# Decoder.net
KiCad netlist of a schematic drawn in EAGLE
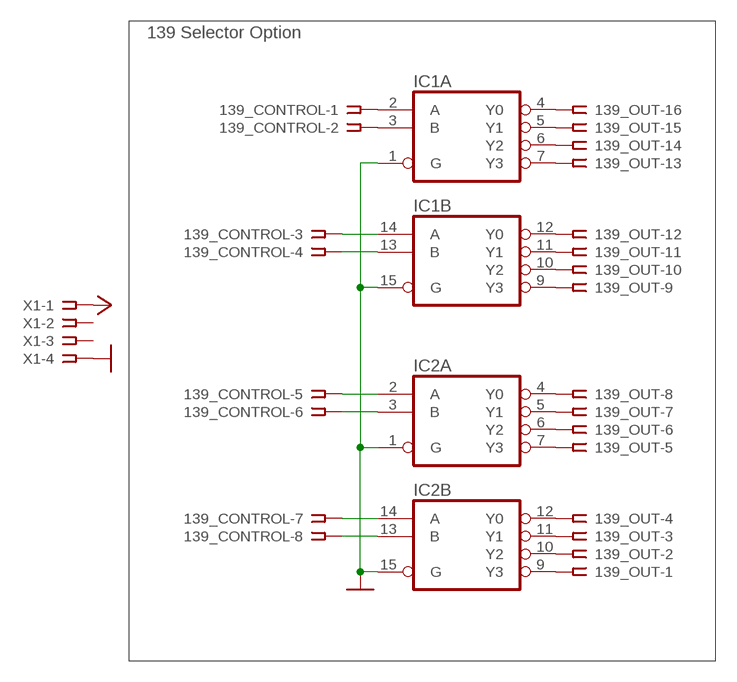
[diagram p0: schematic, sheet 1]

(export (version "E")
  (design (tool "Eeschema 10.0.6"))
  (components
    (comp (ref "139_CONTROL")
      (value "SSW-108-02-G-S")
      (footprint "eagle-import:SSW-108-02-G-S")
      (fields (field (name "MF") "Samtec Inc."))
      (libsource (lib "eagle-import") (part "SSW-108-02-G-S"))
    )
    (comp (ref "139_OUT")
      (value "SSW-116-02-G-S")
      (footprint "eagle-import:SSW-116-02-G-S")
      (fields (field (name "MF") "Samtec Inc."))
      (libsource (lib "eagle-import") (part "SSW-116-02-G-S"))
    )
    (comp (ref "IC1")
      (value "74AC139N")
      (footprint "eagle-import:DIL16")
      (libsource (lib "eagle-import") (part "74139NAC"))
    )
    (comp (ref "IC2")
      (value "74AC139N")
      (footprint "eagle-import:DIL16")
      (libsource (lib "eagle-import") (part "74139NAC"))
    )
    (comp (ref "X1")
      (value "SSW-104-02-G-S")
      (footprint "eagle-import:SSW-104-02-G-S")
      (fields (field (name "MF") "Samtec Inc."))
      (libsource (lib "eagle-import") (part "SSW-104-02-G-S"))
    )
  )
  (nets
    (net (code "1") (name "GND") (class "Default")
      (node (ref "IC1") (pin "1") (pinfunction "G_1") (pintype "input"))
      (node (ref "IC1") (pin "15") (pinfunction "G_15") (pintype "input"))
      (node (ref "IC2") (pin "1") (pinfunction "G_1") (pintype "input"))
      (node (ref "IC2") (pin "15") (pinfunction "G_15") (pintype "input"))
      (node (ref "X1") (pin "4") (pinfunction "1_4") (pintype "passive"))
    )
    (net (code "2") (name "Net-(139_CONTROLB-1)") (class "Default")
      (node (ref "139_CONTROL") (pin "2") (pinfunction "1_2") (pintype "passive"))
      (node (ref "IC1") (pin "3") (pinfunction "B_3") (pintype "input"))
    )
    (net (code "3") (name "Net-(139_CONTROLC-1)") (class "Default")
      (node (ref "139_CONTROL") (pin "3") (pinfunction "1_3") (pintype "passive"))
      (node (ref "IC1") (pin "14") (pinfunction "A_14") (pintype "input"))
    )
    (net (code "4") (name "Net-(139_CONTROLD-1)") (class "Default")
      (node (ref "139_CONTROL") (pin "4") (pinfunction "1_4") (pintype "passive"))
      (node (ref "IC1") (pin "13") (pinfunction "B_13") (pintype "input"))
    )
    (net (code "5") (name "Net-(139_CONTROLE-1)") (class "Default")
      (node (ref "139_CONTROL") (pin "5") (pinfunction "1_5") (pintype "passive"))
      (node (ref "IC2") (pin "2") (pinfunction "A_2") (pintype "input"))
    )
    (net (code "6") (name "Net-(139_CONTROLF-1)") (class "Default")
      (node (ref "139_CONTROL") (pin "6") (pinfunction "1_6") (pintype "passive"))
      (node (ref "IC2") (pin "3") (pinfunction "B_3") (pintype "input"))
    )
    (net (code "7") (name "Net-(139_CONTROLG-1)") (class "Default")
      (node (ref "139_CONTROL") (pin "7") (pinfunction "1_7") (pintype "passive"))
      (node (ref "IC2") (pin "14") (pinfunction "A_14") (pintype "input"))
    )
    (net (code "8") (name "Net-(139_CONTROLH-1)") (class "Default")
      (node (ref "139_CONTROL") (pin "8") (pinfunction "1_8") (pintype "passive"))
      (node (ref "IC2") (pin "13") (pinfunction "B_13") (pintype "input"))
    )
    (net (code "9") (name "Net-(139_OUTB-1)") (class "Default")
      (node (ref "139_OUT") (pin "10") (pinfunction "1_10") (pintype "passive"))
      (node (ref "IC1") (pin "10") (pinfunction "Y2_10") (pintype "output"))
    )
    (net (code "10") (name "Net-(139_OUTC-1)") (class "Default")
      (node (ref "139_OUT") (pin "11") (pinfunction "1_11") (pintype "passive"))
      (node (ref "IC1") (pin "11") (pinfunction "Y1_11") (pintype "output"))
    )
    (net (code "11") (name "Net-(139_OUTD-1)") (class "Default")
      (node (ref "139_OUT") (pin "12") (pinfunction "1_12") (pintype "passive"))
      (node (ref "IC1") (pin "12") (pinfunction "Y0_12") (pintype "output"))
    )
    (net (code "12") (name "Net-(139_OUTE-1)") (class "Default")
      (node (ref "139_OUT") (pin "13") (pinfunction "1_13") (pintype "passive"))
      (node (ref "IC1") (pin "7") (pinfunction "Y3_7") (pintype "output"))
    )
    (net (code "13") (name "Net-(139_OUTF-1)") (class "Default")
      (node (ref "139_OUT") (pin "14") (pinfunction "1_14") (pintype "passive"))
      (node (ref "IC1") (pin "6") (pinfunction "Y2_6") (pintype "output"))
    )
    (net (code "14") (name "Net-(139_OUTG-1)") (class "Default")
      (node (ref "139_OUT") (pin "15") (pinfunction "1_15") (pintype "passive"))
      (node (ref "IC1") (pin "5") (pinfunction "Y1_5") (pintype "output"))
    )
    (net (code "15") (name "Net-(139_OUTH-1)") (class "Default")
      (node (ref "139_OUT") (pin "16") (pinfunction "1_16") (pintype "passive"))
      (node (ref "IC1") (pin "4") (pinfunction "Y0_4") (pintype "output"))
    )
    (net (code "16") (name "Net-(139_OUTI-1)") (class "Default")
      (node (ref "139_OUT") (pin "2") (pinfunction "1_2") (pintype "passive"))
      (node (ref "IC2") (pin "10") (pinfunction "Y2_10") (pintype "output"))
    )
    (net (code "17") (name "Net-(139_OUTJ-1)") (class "Default")
      (node (ref "139_OUT") (pin "3") (pinfunction "1_3") (pintype "passive"))
      (node (ref "IC2") (pin "11") (pinfunction "Y1_11") (pintype "output"))
    )
    (net (code "18") (name "Net-(139_OUTK-1)") (class "Default")
      (node (ref "139_OUT") (pin "4") (pinfunction "1_4") (pintype "passive"))
      (node (ref "IC2") (pin "12") (pinfunction "Y0_12") (pintype "output"))
    )
    (net (code "19") (name "Net-(139_OUTL-1)") (class "Default")
      (node (ref "139_OUT") (pin "5") (pinfunction "1_5") (pintype "passive"))
      (node (ref "IC2") (pin "7") (pinfunction "Y3_7") (pintype "output"))
    )
    (net (code "20") (name "Net-(139_OUTM-1)") (class "Default")
      (node (ref "139_OUT") (pin "6") (pinfunction "1_6") (pintype "passive"))
      (node (ref "IC2") (pin "6") (pinfunction "Y2_6") (pintype "output"))
    )
    (net (code "21") (name "Net-(139_OUTN-1)") (class "Default")
      (node (ref "139_OUT") (pin "7") (pinfunction "1_7") (pintype "passive"))
      (node (ref "IC2") (pin "5") (pinfunction "Y1_5") (pintype "output"))
    )
    (net (code "22") (name "Net-(139_OUTO-1)") (class "Default")
      (node (ref "139_OUT") (pin "8") (pinfunction "1_8") (pintype "passive"))
      (node (ref "IC2") (pin "4") (pinfunction "Y0_4") (pintype "output"))
    )
    (net (code "23") (name "Net-(139_OUTP-1)") (class "Default")
      (node (ref "139_OUT") (pin "9") (pinfunction "1_9") (pintype "passive"))
      (node (ref "IC1") (pin "9") (pinfunction "Y3_9") (pintype "output"))
    )
    (net (code "24") (name "Net-(IC1A-A)") (class "Default")
      (node (ref "139_CONTROL") (pin "1") (pinfunction "1_1") (pintype "passive"))
      (node (ref "IC1") (pin "2") (pinfunction "A_2") (pintype "input"))
    )
    (net (code "25") (name "Net-(IC2B-Y3)") (class "Default")
      (node (ref "139_OUT") (pin "1") (pinfunction "1_1") (pintype "passive"))
      (node (ref "IC2") (pin "9") (pinfunction "Y3_9") (pintype "output"))
    )
    (net (code "26") (name "VCC") (class "Default")
      (node (ref "X1") (pin "1") (pinfunction "1_1") (pintype "passive"))
    )
    (net (code "27") (name "unconnected-(X1B-1-Pad2)") (class "Default")
      (node (ref "X1") (pin "2") (pinfunction "1_2") (pintype "passive"))
    )
    (net (code "28") (name "unconnected-(X1C-1-Pad3)") (class "Default")
      (node (ref "X1") (pin "3") (pinfunction "1_3") (pintype "passive"))
    )
  )
)
